# Sheet1.net
KiCad netlist of a schematic drawn in Altium Designer
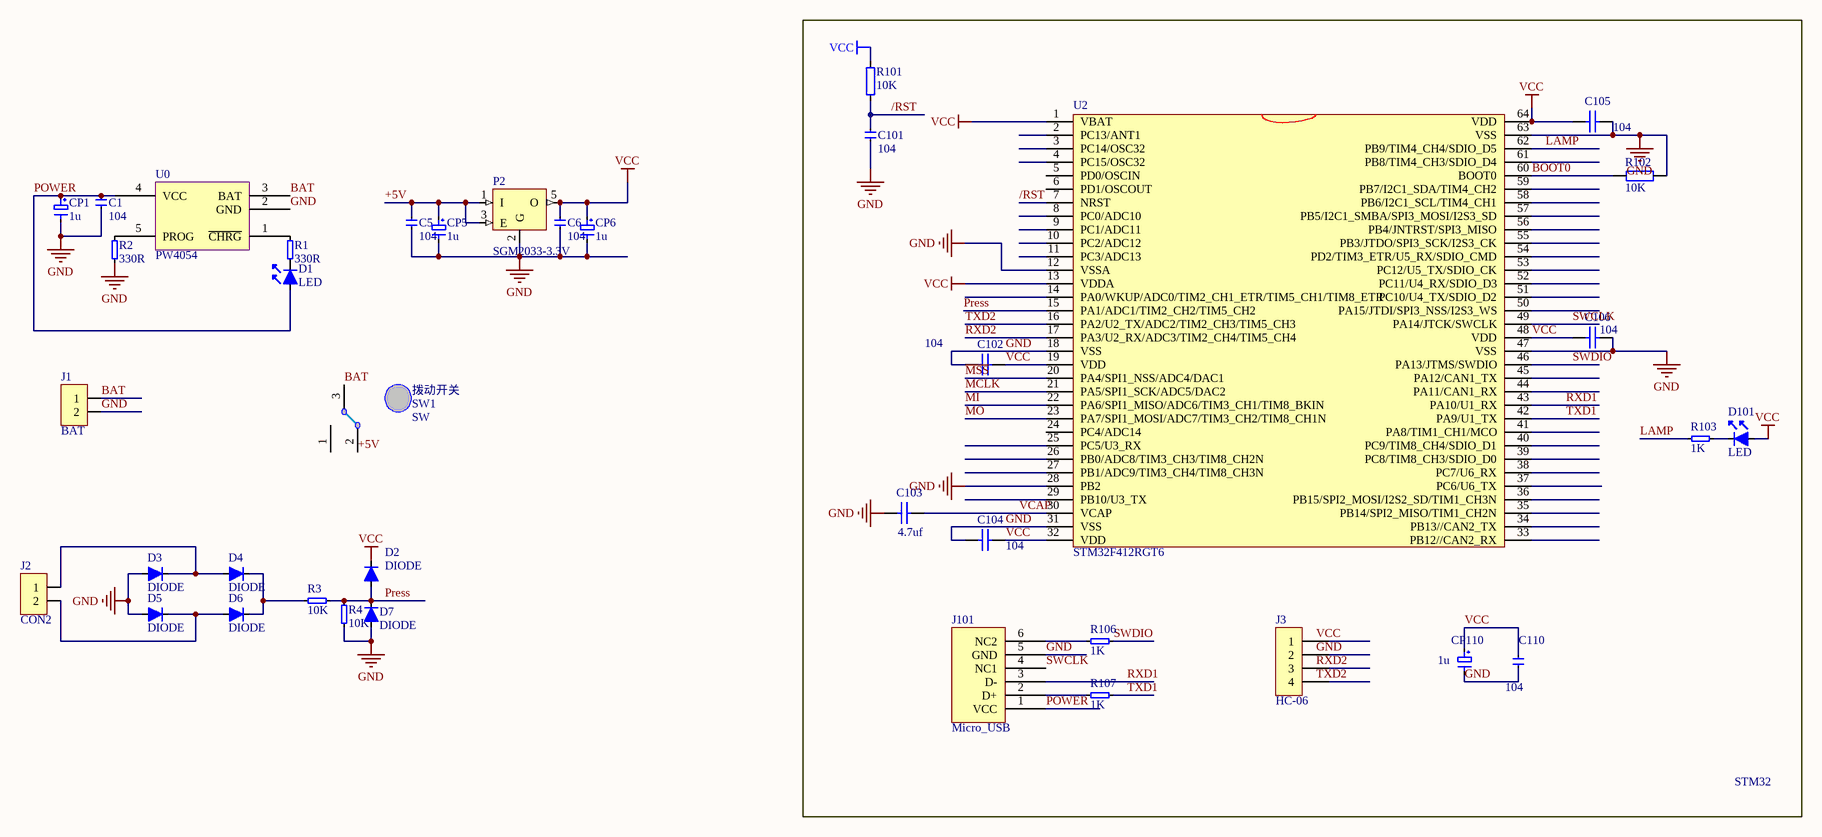
[diagram p0: Sheet1.SchDoc]

(export (version "E")
  (design (tool "Eeschema 10.0.6"))
  (components
    (comp (ref "C1")
      (value "104")
      (footprint "0805")
      (description "CAP")
      (libsource (lib "Schlib") (part "CAP"))
    )
    (comp (ref "C5") (value "104") (footprint "0805") (description "1uF") (libsource (lib "zj") (part "CAP")))
    (comp (ref "C6") (value "104") (footprint "0805") (description "1uF") (libsource (lib "zj") (part "CAP")))
    (comp (ref "C101")
      (value "104")
      (footprint "0603")
      (description "CAP")
      (libsource (lib "*") (part "CAP"))
    )
    (comp (ref "C102")
      (value "104")
      (footprint "0603")
      (description "Capacitor")
      (fields (field (name "Comment") "50V22pF") (field (name "PUBLISHER") "Altium Limited"))
      (libsource (lib "SUPERWDS") (part "Cap1"))
    )
    (comp (ref "C103")
      (value "4.7uf")
      (footprint "0603")
      (description "Capacitor")
      (fields (field (name "Comment") "50V22pF") (field (name "PUBLISHER") "Altium Limited"))
      (libsource (lib "SUPERWDS") (part "Cap1"))
    )
    (comp (ref "C104")
      (value "104")
      (footprint "0603")
      (description "Capacitor")
      (fields (field (name "Comment") "50V22pF") (field (name "PUBLISHER") "Altium Limited"))
      (libsource (lib "SUPERWDS") (part "Cap1"))
    )
    (comp (ref "C105")
      (value "104")
      (footprint "0603")
      (description "Capacitor")
      (fields (field (name "Comment") "50V22pF") (field (name "PUBLISHER") "Altium Limited"))
      (libsource (lib "SUPERWDS") (part "Cap1"))
    )
    (comp (ref "C106")
      (value "104")
      (footprint "0603")
      (description "Capacitor")
      (fields (field (name "Comment") "50V22pF") (field (name "PUBLISHER") "Altium Limited"))
      (libsource (lib "SUPERWDS") (part "Cap1"))
    )
    (comp (ref "C110")
      (value "104")
      (footprint "0805")
      (description "CAP")
      (libsource (lib "*") (part "CAP"))
    )
    (comp (ref "CP1")
      (value "1u")
      (footprint "0805")
      (description "CAP+")
      (libsource (lib "Schlib") (part "CAP+"))
    )
    (comp (ref "CP5")
      (value "1u")
      (footprint "0805")
      (description "CAP+")
      (libsource (lib "zj") (part "CAP+"))
    )
    (comp (ref "CP6")
      (value "1u")
      (footprint "0805")
      (description "CAP+")
      (libsource (lib "zj") (part "CAP+"))
    )
    (comp (ref "CP110")
      (value "1u")
      (footprint "0805")
      (description "CAP+")
      (libsource (lib "*") (part "CAP+"))
    )
    (comp (ref "D1")
      (value "LED")
      (footprint "LEDDIP")
      (description "LAMP")
      (libsource (lib "Schlib") (part "LAMP"))
    )
    (comp (ref "D2") (value "DIODE") (footprint "0805") (libsource (lib "swgLIB") (part "DIODE")))
    (comp (ref "D3") (value "DIODE") (footprint "0805") (libsource (lib "swgLIB") (part "DIODE")))
    (comp (ref "D4") (value "DIODE") (footprint "0805") (libsource (lib "swgLIB") (part "DIODE")))
    (comp (ref "D5") (value "DIODE") (footprint "0805") (libsource (lib "swgLIB") (part "DIODE")))
    (comp (ref "D6") (value "DIODE") (footprint "0805") (libsource (lib "swgLIB") (part "DIODE")))
    (comp (ref "D7") (value "DIODE") (footprint "0805") (libsource (lib "swgLIB") (part "DIODE")))
    (comp (ref "D101")
      (value "LED")
      (footprint "LEDDIP")
      (description "LAMP")
      (libsource (lib "swgLIB") (part "LAMP"))
    )
    (comp (ref "J1")
      (value "BAT")
      (footprint "SIP2")
      (description "Conjunctor")
      (libsource (lib "zj") (part "CON2"))
    )
    (comp (ref "J2")
      (value "CON2")
      (footprint "SIP2")
      (description "Conjunctor")
      (libsource (lib "swgLIB") (part "CON2"))
    )
    (comp (ref "J3")
      (value "HC-06")
      (footprint "SIP4")
      (description "CON4")
      (libsource (lib "swgLIB") (part "CON4"))
    )
    (comp (ref "J101")
      (value "Micro_USB")
      (footprint "MICRO-USB")
      (libsource (lib "Schlib") (part "Micro_USB"))
    )
    (comp (ref "P2") (value "SGM2033-3.3V") (footprint "SOT23-5") (libsource (lib "zj") (part "SGM2033")))
    (comp (ref "R1")
      (value "330R")
      (footprint "0603")
      (description "RES")
      (libsource (lib "Schlib") (part "RES"))
    )
    (comp (ref "R2")
      (value "330R")
      (footprint "0603")
      (description "RES")
      (libsource (lib "Schlib") (part "RES"))
    )
    (comp (ref "R3")
      (value "10K")
      (footprint "0805")
      (description "RES")
      (libsource (lib "swgLIB") (part "RES"))
    )
    (comp (ref "R4")
      (value "10K")
      (footprint "0805")
      (description "RES")
      (libsource (lib "swgLIB") (part "RES"))
    )
    (comp (ref "R101")
      (value "10K")
      (footprint "0603")
      (description "RES")
      (libsource (lib "*") (part "RESISTANCE"))
    )
    (comp (ref "R102") (value "10K") (footprint "0603") (libsource (lib "MiniSTM32底板_SCH") (part "R")))
    (comp (ref "R103")
      (value "1K")
      (footprint "0603")
      (description "RES")
      (libsource (lib "swgLIB") (part "RES"))
    )
    (comp (ref "R106")
      (value "1K")
      (footprint "0603")
      (description "RES")
      (libsource (lib "swgLIB") (part "RES"))
    )
    (comp (ref "R107")
      (value "1K")
      (footprint "0603")
      (description "RES")
      (libsource (lib "swgLIB") (part "RES"))
    )
    (comp (ref "SW1") (value "SW") (footprint "SW3") (libsource (lib "Schlib") (part "SW")))
    (comp (ref "U0") (value "PW4054") (footprint "SOT23-5") (libsource (lib "Schlib") (part "PW4054")))
    (comp (ref "U2")
      (value "STM32F412RGT6")
      (footprint "LQFP64")
      (libsource (lib "shu") (part "STM32F412RGT6"))
    )
  )
  (nets
    (net (code "1") (name "/+5V") (class "Default")
      (node (ref "C5") (pin "1") (pinfunction "1_1") (pintype "passive"))
      (node (ref "CP5") (pin "1") (pinfunction "1_1") (pintype "passive"))
      (node (ref "P2") (pin "1") (pinfunction "I_1") (pintype "input"))
      (node (ref "P2") (pin "3") (pinfunction "E_3") (pintype "input"))
      (node (ref "SW1") (pin "2") (pinfunction "2_2") (pintype "passive"))
    )
    (net (code "2") (name "/BAT") (class "Default")
      (node (ref "J1") (pin "1") (pinfunction "1_1") (pintype "passive"))
      (node (ref "SW1") (pin "3") (pinfunction "3_3") (pintype "passive"))
      (node (ref "U0") (pin "3") (pinfunction "BAT_3") (pintype "passive"))
    )
    (net (code "3") (name "/BOOT0") (class "Default")
      (node (ref "R102") (pin "1") (pintype "passive"))
      (node (ref "U2") (pin "60") (pinfunction "BOOT0_60") (pintype "passive"))
    )
    (net (code "4") (name "/LAMP") (class "Default")
      (node (ref "R103") (pin "1") (pinfunction "1_1") (pintype "passive"))
      (node (ref "U2") (pin "62") (pinfunction "PB9/TIM4_CH4/SDIO_D5_62") (pintype "passive"))
    )
    (net (code "5") (name "/MCLK") (class "Default")
      (node (ref "U2") (pin "21") (pinfunction "PA5/SPI1_SCK/ADC5/DAC2_21") (pintype "passive"))
    )
    (net (code "6") (name "/MI") (class "Default")
      (node (ref "U2") (pin "22") (pinfunction "PA6/SPI1_MISO/ADC6/TIM3_CH1/TIM8_BKIN_22") (pintype "passive"))
    )
    (net (code "7") (name "/MO") (class "Default")
      (node (ref "U2") (pin "23") (pinfunction "PA7/SPI1_MOSI/ADC7/TIM3_CH2/TIM8_CH1N_23") (pintype "passive"))
    )
    (net (code "8") (name "/POWER") (class "Default")
      (node (ref "C1") (pin "1") (pinfunction "1_1") (pintype "passive"))
      (node (ref "CP1") (pin "1") (pinfunction "1_1") (pintype "passive"))
      (node (ref "D1") (pin "1") (pinfunction "A_1") (pintype "passive"))
      (node (ref "J101") (pin "1") (pinfunction "VCC_1") (pintype "passive"))
      (node (ref "U0") (pin "4") (pinfunction "VCC_4") (pintype "passive"))
    )
    (net (code "9") (name "/Press") (class "Default")
      (node (ref "D2") (pin "1") (pinfunction "A_1") (pintype "passive"))
      (node (ref "D7") (pin "2") (pinfunction "K_2") (pintype "passive"))
      (node (ref "R3") (pin "1") (pinfunction "1_1") (pintype "passive"))
      (node (ref "R4") (pin "1") (pinfunction "1_1") (pintype "passive"))
      (node (ref "U2") (pin "15") (pinfunction "PA1/ADC1/TIM2_CH2/TIM5_CH2_15") (pintype "passive"))
    )
    (net (code "10") (name "/RXD1") (class "Default")
      (node (ref "J101") (pin "3") (pinfunction "D-_3") (pintype "passive"))
      (node (ref "U2") (pin "43") (pinfunction "PA10/U1_RX_43") (pintype "passive"))
    )
    (net (code "11") (name "/RXD2") (class "Default")
      (node (ref "U2") (pin "17") (pinfunction "PA3/U2_RX/ADC3/TIM2_CH4/TIM5_CH4_17") (pintype "passive"))
    )
    (net (code "12") (name "/SWCLK") (class "Default")
      (node (ref "J101") (pin "4") (pinfunction "NC1_4") (pintype "passive"))
      (node (ref "U2") (pin "49") (pinfunction "PA14/JTCK/SWCLK_49") (pintype "passive"))
    )
    (net (code "13") (name "/SWDIO") (class "Default")
      (node (ref "R106") (pin "2") (pinfunction "2_2") (pintype "passive"))
      (node (ref "U2") (pin "46") (pinfunction "PA13/JTMS/SWDIO_46") (pintype "passive"))
    )
    (net (code "14") (name "/TXD1") (class "Default")
      (node (ref "R107") (pin "2") (pinfunction "2_2") (pintype "passive"))
      (node (ref "U2") (pin "42") (pinfunction "PA9/U1_TX_42") (pintype "passive"))
    )
    (net (code "15") (name "/TXD2") (class "Default")
      (node (ref "U2") (pin "16") (pinfunction "PA2/U2_TX/ADC2/TIM2_CH3/TIM5_CH3_16") (pintype "passive"))
    )
    (net (code "16") (name "/VCAP") (class "Default")
      (node (ref "C103") (pin "1") (pinfunction "1_1") (pintype "passive"))
      (node (ref "U2") (pin "30") (pinfunction "VCAP_30") (pintype "passive"))
    )
    (net (code "17") (name "/{slash}RST") (class "Default")
      (node (ref "C101") (pin "1") (pinfunction "1_1") (pintype "passive"))
      (node (ref "R101") (pin "2") (pinfunction "2_2") (pintype "passive"))
      (node (ref "U2") (pin "7") (pinfunction "NRST_7") (pintype "passive"))
    )
    (net (code "18") (name "/~{MSS}") (class "Default")
      (node (ref "U2") (pin "20") (pinfunction "PA4/SPI1_NSS/ADC4/DAC1_20") (pintype "passive"))
    )
    (net (code "19") (name "GND") (class "Default")
      (node (ref "C1") (pin "2") (pinfunction "2_2") (pintype "passive"))
      (node (ref "C101") (pin "2") (pinfunction "2_2") (pintype "passive"))
      (node (ref "C102") (pin "2") (pinfunction "2_2") (pintype "passive"))
      (node (ref "C103") (pin "2") (pinfunction "2_2") (pintype "passive"))
      (node (ref "C104") (pin "2") (pinfunction "2_2") (pintype "passive"))
      (node (ref "C105") (pin "1") (pinfunction "1_1") (pintype "passive"))
      (node (ref "C106") (pin "1") (pinfunction "1_1") (pintype "passive"))
      (node (ref "C110") (pin "2") (pinfunction "2_2") (pintype "passive"))
      (node (ref "C5") (pin "2") (pinfunction "2_2") (pintype "passive"))
      (node (ref "C6") (pin "2") (pinfunction "2_2") (pintype "passive"))
      (node (ref "CP1") (pin "2") (pinfunction "2_2") (pintype "passive"))
      (node (ref "CP110") (pin "2") (pinfunction "2_2") (pintype "passive"))
      (node (ref "CP5") (pin "2") (pinfunction "2_2") (pintype "passive"))
      (node (ref "CP6") (pin "2") (pinfunction "2_2") (pintype "passive"))
      (node (ref "D3") (pin "1") (pinfunction "A_1") (pintype "passive"))
      (node (ref "D5") (pin "1") (pinfunction "A_1") (pintype "passive"))
      (node (ref "D7") (pin "1") (pinfunction "A_1") (pintype "passive"))
      (node (ref "J1") (pin "2") (pinfunction "2_2") (pintype "passive"))
      (node (ref "J101") (pin "5") (pinfunction "GND_5") (pintype "passive"))
      (node (ref "P2") (pin "2") (pinfunction "G_2") (pintype "passive"))
      (node (ref "R102") (pin "2") (pintype "passive"))
      (node (ref "R2") (pin "1") (pinfunction "1_1") (pintype "passive"))
      (node (ref "R4") (pin "2") (pinfunction "2_2") (pintype "passive"))
      (node (ref "U0") (pin "2") (pinfunction "GND_2") (pintype "passive"))
      (node (ref "U2") (pin "12") (pinfunction "VSSA_12") (pintype "passive"))
      (node (ref "U2") (pin "18") (pinfunction "VSS_18") (pintype "passive"))
      (node (ref "U2") (pin "28") (pinfunction "PB2_28") (pintype "passive"))
      (node (ref "U2") (pin "31") (pinfunction "VSS_31") (pintype "passive"))
      (node (ref "U2") (pin "47") (pinfunction "VSS_47") (pintype "passive"))
      (node (ref "U2") (pin "63") (pinfunction "VSS_63") (pintype "passive"))
    )
    (net (code "20") (name "Net-(D1-K)") (class "Default")
      (node (ref "D1") (pin "2") (pinfunction "K_2") (pintype "passive"))
      (node (ref "R1") (pin "1") (pinfunction "1_1") (pintype "passive"))
    )
    (net (code "21") (name "Net-(D3-K)") (class "Default")
      (node (ref "D3") (pin "2") (pinfunction "K_2") (pintype "passive"))
      (node (ref "D4") (pin "1") (pinfunction "A_1") (pintype "passive"))
      (node (ref "J2") (pin "1") (pinfunction "1_1") (pintype "passive"))
    )
    (net (code "22") (name "Net-(D4-K)") (class "Default")
      (node (ref "D4") (pin "2") (pinfunction "K_2") (pintype "passive"))
      (node (ref "D6") (pin "2") (pinfunction "K_2") (pintype "passive"))
      (node (ref "R3") (pin "2") (pinfunction "2_2") (pintype "passive"))
    )
    (net (code "23") (name "Net-(D5-K)") (class "Default")
      (node (ref "D5") (pin "2") (pinfunction "K_2") (pintype "passive"))
      (node (ref "D6") (pin "1") (pinfunction "A_1") (pintype "passive"))
      (node (ref "J2") (pin "2") (pinfunction "2_2") (pintype "passive"))
    )
    (net (code "24") (name "Net-(D101-K)") (class "Default")
      (node (ref "D101") (pin "2") (pinfunction "K_2") (pintype "passive"))
      (node (ref "R103") (pin "2") (pinfunction "2_2") (pintype "passive"))
    )
    (net (code "25") (name "Net-(J101-D+)") (class "Default")
      (node (ref "J101") (pin "2") (pinfunction "D+_2") (pintype "passive"))
      (node (ref "R107") (pin "1") (pinfunction "1_1") (pintype "passive"))
    )
    (net (code "26") (name "Net-(J101-NC2)") (class "Default")
      (node (ref "J101") (pin "6") (pinfunction "NC2_6") (pintype "passive"))
      (node (ref "R106") (pin "1") (pinfunction "1_1") (pintype "passive"))
    )
    (net (code "27") (name "Net-(U0-PROG)") (class "Default")
      (node (ref "R2") (pin "2") (pinfunction "2_2") (pintype "passive"))
      (node (ref "U0") (pin "5") (pinfunction "PROG_5") (pintype "passive"))
    )
    (net (code "28") (name "Net-(U0-~{CHRG})") (class "Default")
      (node (ref "R1") (pin "2") (pinfunction "2_2") (pintype "passive"))
      (node (ref "U0") (pin "1") (pinfunction "~{CHRG}_1") (pintype "passive"))
    )
    (net (code "29") (name "VCC") (class "Default")
      (node (ref "C102") (pin "1") (pinfunction "1_1") (pintype "passive"))
      (node (ref "C104") (pin "1") (pinfunction "1_1") (pintype "passive"))
      (node (ref "C105") (pin "2") (pinfunction "2_2") (pintype "passive"))
      (node (ref "C106") (pin "2") (pinfunction "2_2") (pintype "passive"))
      (node (ref "C110") (pin "1") (pinfunction "1_1") (pintype "passive"))
      (node (ref "C6") (pin "1") (pinfunction "1_1") (pintype "passive"))
      (node (ref "CP110") (pin "1") (pinfunction "1_1") (pintype "passive"))
      (node (ref "CP6") (pin "1") (pinfunction "1_1") (pintype "passive"))
      (node (ref "D101") (pin "1") (pinfunction "A_1") (pintype "passive"))
      (node (ref "D2") (pin "2") (pinfunction "K_2") (pintype "passive"))
      (node (ref "P2") (pin "5") (pinfunction "O_5") (pintype "output"))
      (node (ref "R101") (pin "1") (pinfunction "1_1") (pintype "passive"))
      (node (ref "U2") (pin "1") (pinfunction "VBAT_1") (pintype "passive"))
      (node (ref "U2") (pin "13") (pinfunction "VDDA_13") (pintype "passive"))
      (node (ref "U2") (pin "19") (pinfunction "VDD_19") (pintype "passive"))
      (node (ref "U2") (pin "32") (pinfunction "VDD_32") (pintype "passive"))
      (node (ref "U2") (pin "48") (pinfunction "VDD_48") (pintype "passive"))
      (node (ref "U2") (pin "64") (pinfunction "VDD_64") (pintype "passive"))
    )
    (net (code "30") (name "unconnected-(J3-Pad1)") (class "Default")
      (node (ref "J3") (pin "1") (pinfunction "1_1") (pintype "passive"))
    )
    (net (code "31") (name "unconnected-(J3-Pad2)") (class "Default")
      (node (ref "J3") (pin "2") (pinfunction "2_2") (pintype "passive"))
    )
    (net (code "32") (name "unconnected-(J3-Pad3)") (class "Default")
      (node (ref "J3") (pin "3") (pinfunction "3_3") (pintype "passive"))
    )
    (net (code "33") (name "unconnected-(J3-Pad4)") (class "Default")
      (node (ref "J3") (pin "4") (pinfunction "4_4") (pintype "passive"))
    )
    (net (code "34") (name "unconnected-(SW1-Pad1)") (class "Default")
      (node (ref "SW1") (pin "1") (pinfunction "1_1") (pintype "passive"))
    )
    (net (code "35") (name "unconnected-(U2-PA0{slash}WKUP{slash}ADC0{slash}TIM2_CH1_ETR{slash}TIM5_CH1{slash}TIM8_ETR-Pad14)") (class "Default")
      (node (ref "U2") (pin "14") (pinfunction "PA0/WKUP/ADC0/TIM2_CH1_ETR/TIM5_CH1/TIM8_ETR_14") (pintype "passive"))
    )
    (net (code "36") (name "unconnected-(U2-PA8{slash}TIM1_CH1{slash}MCO-Pad41)") (class "Default")
      (node (ref "U2") (pin "41") (pinfunction "PA8/TIM1_CH1/MCO_41") (pintype "passive"))
    )
    (net (code "37") (name "unconnected-(U2-PA11{slash}CAN1_RX-Pad44)") (class "Default")
      (node (ref "U2") (pin "44") (pinfunction "PA11/CAN1_RX_44") (pintype "passive"))
    )
    (net (code "38") (name "unconnected-(U2-PA12{slash}CAN1_TX-Pad45)") (class "Default")
      (node (ref "U2") (pin "45") (pinfunction "PA12/CAN1_TX_45") (pintype "passive"))
    )
    (net (code "39") (name "unconnected-(U2-PA15{slash}JTDI{slash}SPI3_NSS{slash}I2S3_WS-Pad50)") (class "Default")
      (node (ref "U2") (pin "50") (pinfunction "PA15/JTDI/SPI3_NSS/I2S3_WS_50") (pintype "passive"))
    )
    (net (code "40") (name "unconnected-(U2-PB0{slash}ADC8{slash}TIM3_CH3{slash}TIM8_CH2N-Pad26)") (class "Default")
      (node (ref "U2") (pin "26") (pinfunction "PB0/ADC8/TIM3_CH3/TIM8_CH2N_26") (pintype "passive"))
    )
    (net (code "41") (name "unconnected-(U2-PB1{slash}ADC9{slash}TIM3_CH4{slash}TIM8_CH3N-Pad27)") (class "Default")
      (node (ref "U2") (pin "27") (pinfunction "PB1/ADC9/TIM3_CH4/TIM8_CH3N_27") (pintype "passive"))
    )
    (net (code "42") (name "unconnected-(U2-PB3{slash}JTDO{slash}SPI3_SCK{slash}I2S3_CK-Pad55)") (class "Default")
      (node (ref "U2") (pin "55") (pinfunction "PB3/JTDO/SPI3_SCK/I2S3_CK_55") (pintype "passive"))
    )
    (net (code "43") (name "unconnected-(U2-PB4{slash}JNTRST{slash}SPI3_MISO-Pad56)") (class "Default")
      (node (ref "U2") (pin "56") (pinfunction "PB4/JNTRST/SPI3_MISO_56") (pintype "passive"))
    )
    (net (code "44") (name "unconnected-(U2-PB5{slash}I2C1_SMBA{slash}SPI3_MOSI{slash}I2S3_SD-Pad57)") (class "Default")
      (node (ref "U2") (pin "57") (pinfunction "PB5/I2C1_SMBA/SPI3_MOSI/I2S3_SD_57") (pintype "passive"))
    )
    (net (code "45") (name "unconnected-(U2-PB6{slash}I2C1_SCL{slash}TIM4_CH1-Pad58)") (class "Default")
      (node (ref "U2") (pin "58") (pinfunction "PB6/I2C1_SCL/TIM4_CH1_58") (pintype "passive"))
    )
    (net (code "46") (name "unconnected-(U2-PB7{slash}I2C1_SDA{slash}TIM4_CH2-Pad59)") (class "Default")
      (node (ref "U2") (pin "59") (pinfunction "PB7/I2C1_SDA/TIM4_CH2_59") (pintype "passive"))
    )
    (net (code "47") (name "unconnected-(U2-PB8{slash}TIM4_CH3{slash}SDIO_D4-Pad61)") (class "Default")
      (node (ref "U2") (pin "61") (pinfunction "PB8/TIM4_CH3/SDIO_D4_61") (pintype "passive"))
    )
    (net (code "48") (name "unconnected-(U2-PB10{slash}U3_TX-Pad29)") (class "Default")
      (node (ref "U2") (pin "29") (pinfunction "PB10/U3_TX_29") (pintype "passive"))
    )
    (net (code "49") (name "unconnected-(U2-PB12{slash}{slash}CAN2_RX-Pad33)") (class "Default")
      (node (ref "U2") (pin "33") (pinfunction "PB12//CAN2_RX_33") (pintype "passive"))
    )
    (net (code "50") (name "unconnected-(U2-PB13{slash}{slash}CAN2_TX-Pad34)") (class "Default")
      (node (ref "U2") (pin "34") (pinfunction "PB13//CAN2_TX_34") (pintype "passive"))
    )
    (net (code "51") (name "unconnected-(U2-PB14{slash}SPI2_MISO{slash}TIM1_CH2N-Pad35)") (class "Default")
      (node (ref "U2") (pin "35") (pinfunction "PB14/SPI2_MISO/TIM1_CH2N_35") (pintype "passive"))
    )
    (net (code "52") (name "unconnected-(U2-PB15{slash}SPI2_MOSI{slash}I2S2_SD{slash}TIM1_CH3N-Pad36)") (class "Default")
      (node (ref "U2") (pin "36") (pinfunction "PB15/SPI2_MOSI/I2S2_SD/TIM1_CH3N_36") (pintype "passive"))
    )
    (net (code "53") (name "unconnected-(U2-PC0{slash}ADC10-Pad8)") (class "Default")
      (node (ref "U2") (pin "8") (pinfunction "PC0/ADC10_8") (pintype "passive"))
    )
    (net (code "54") (name "unconnected-(U2-PC1{slash}ADC11-Pad9)") (class "Default")
      (node (ref "U2") (pin "9") (pinfunction "PC1/ADC11_9") (pintype "passive"))
    )
    (net (code "55") (name "unconnected-(U2-PC2{slash}ADC12-Pad10)") (class "Default")
      (node (ref "U2") (pin "10") (pinfunction "PC2/ADC12_10") (pintype "passive"))
    )
    (net (code "56") (name "unconnected-(U2-PC3{slash}ADC13-Pad11)") (class "Default")
      (node (ref "U2") (pin "11") (pinfunction "PC3/ADC13_11") (pintype "passive"))
    )
    (net (code "57") (name "unconnected-(U2-PC4{slash}ADC14-Pad24)") (class "Default")
      (node (ref "U2") (pin "24") (pinfunction "PC4/ADC14_24") (pintype "passive"))
    )
    (net (code "58") (name "unconnected-(U2-PC5{slash}U3_RX-Pad25)") (class "Default")
      (node (ref "U2") (pin "25") (pinfunction "PC5/U3_RX_25") (pintype "passive"))
    )
    (net (code "59") (name "unconnected-(U2-PC6{slash}U6_TX-Pad37)") (class "Default")
      (node (ref "U2") (pin "37") (pinfunction "PC6/U6_TX_37") (pintype "passive"))
    )
    (net (code "60") (name "unconnected-(U2-PC7{slash}U6_RX-Pad38)") (class "Default")
      (node (ref "U2") (pin "38") (pinfunction "PC7/U6_RX_38") (pintype "passive"))
    )
    (net (code "61") (name "unconnected-(U2-PC8{slash}TIM8_CH3{slash}SDIO_D0-Pad39)") (class "Default")
      (node (ref "U2") (pin "39") (pinfunction "PC8/TIM8_CH3/SDIO_D0_39") (pintype "passive"))
    )
    (net (code "62") (name "unconnected-(U2-PC9{slash}TIM8_CH4{slash}SDIO_D1-Pad40)") (class "Default")
      (node (ref "U2") (pin "40") (pinfunction "PC9/TIM8_CH4/SDIO_D1_40") (pintype "passive"))
    )
    (net (code "63") (name "unconnected-(U2-PC10{slash}U4_TX{slash}SDIO_D2-Pad51)") (class "Default")
      (node (ref "U2") (pin "51") (pinfunction "PC10/U4_TX/SDIO_D2_51") (pintype "passive"))
    )
    (net (code "64") (name "unconnected-(U2-PC11{slash}U4_RX{slash}SDIO_D3-Pad52)") (class "Default")
      (node (ref "U2") (pin "52") (pinfunction "PC11/U4_RX/SDIO_D3_52") (pintype "passive"))
    )
    (net (code "65") (name "unconnected-(U2-PC12{slash}U5_TX{slash}SDIO_CK-Pad53)") (class "Default")
      (node (ref "U2") (pin "53") (pinfunction "PC12/U5_TX/SDIO_CK_53") (pintype "passive"))
    )
    (net (code "66") (name "unconnected-(U2-PC13{slash}ANT1-Pad2)") (class "Default")
      (node (ref "U2") (pin "2") (pinfunction "PC13/ANT1_2") (pintype "passive"))
    )
    (net (code "67") (name "unconnected-(U2-PC14{slash}OSC32-Pad3)") (class "Default")
      (node (ref "U2") (pin "3") (pinfunction "PC14/OSC32_3") (pintype "passive"))
    )
    (net (code "68") (name "unconnected-(U2-PC15{slash}OSC32-Pad4)") (class "Default")
      (node (ref "U2") (pin "4") (pinfunction "PC15/OSC32_4") (pintype "passive"))
    )
    (net (code "69") (name "unconnected-(U2-PD0{slash}OSCIN-Pad5)") (class "Default")
      (node (ref "U2") (pin "5") (pinfunction "PD0/OSCIN_5") (pintype "passive"))
    )
    (net (code "70") (name "unconnected-(U2-PD1{slash}OSCOUT-Pad6)") (class "Default")
      (node (ref "U2") (pin "6") (pinfunction "PD1/OSCOUT_6") (pintype "passive"))
    )
    (net (code "71") (name "unconnected-(U2-PD2{slash}TIM3_ETR{slash}U5_RX{slash}SDIO_CMD-Pad54)") (class "Default")
      (node (ref "U2") (pin "54") (pinfunction "PD2/TIM3_ETR/U5_RX/SDIO_CMD_54") (pintype "passive"))
    )
  )
)
